# SCH_usb-hub_2024-06-10.net
KiCad netlist of a schematic drawn in EasyEDA
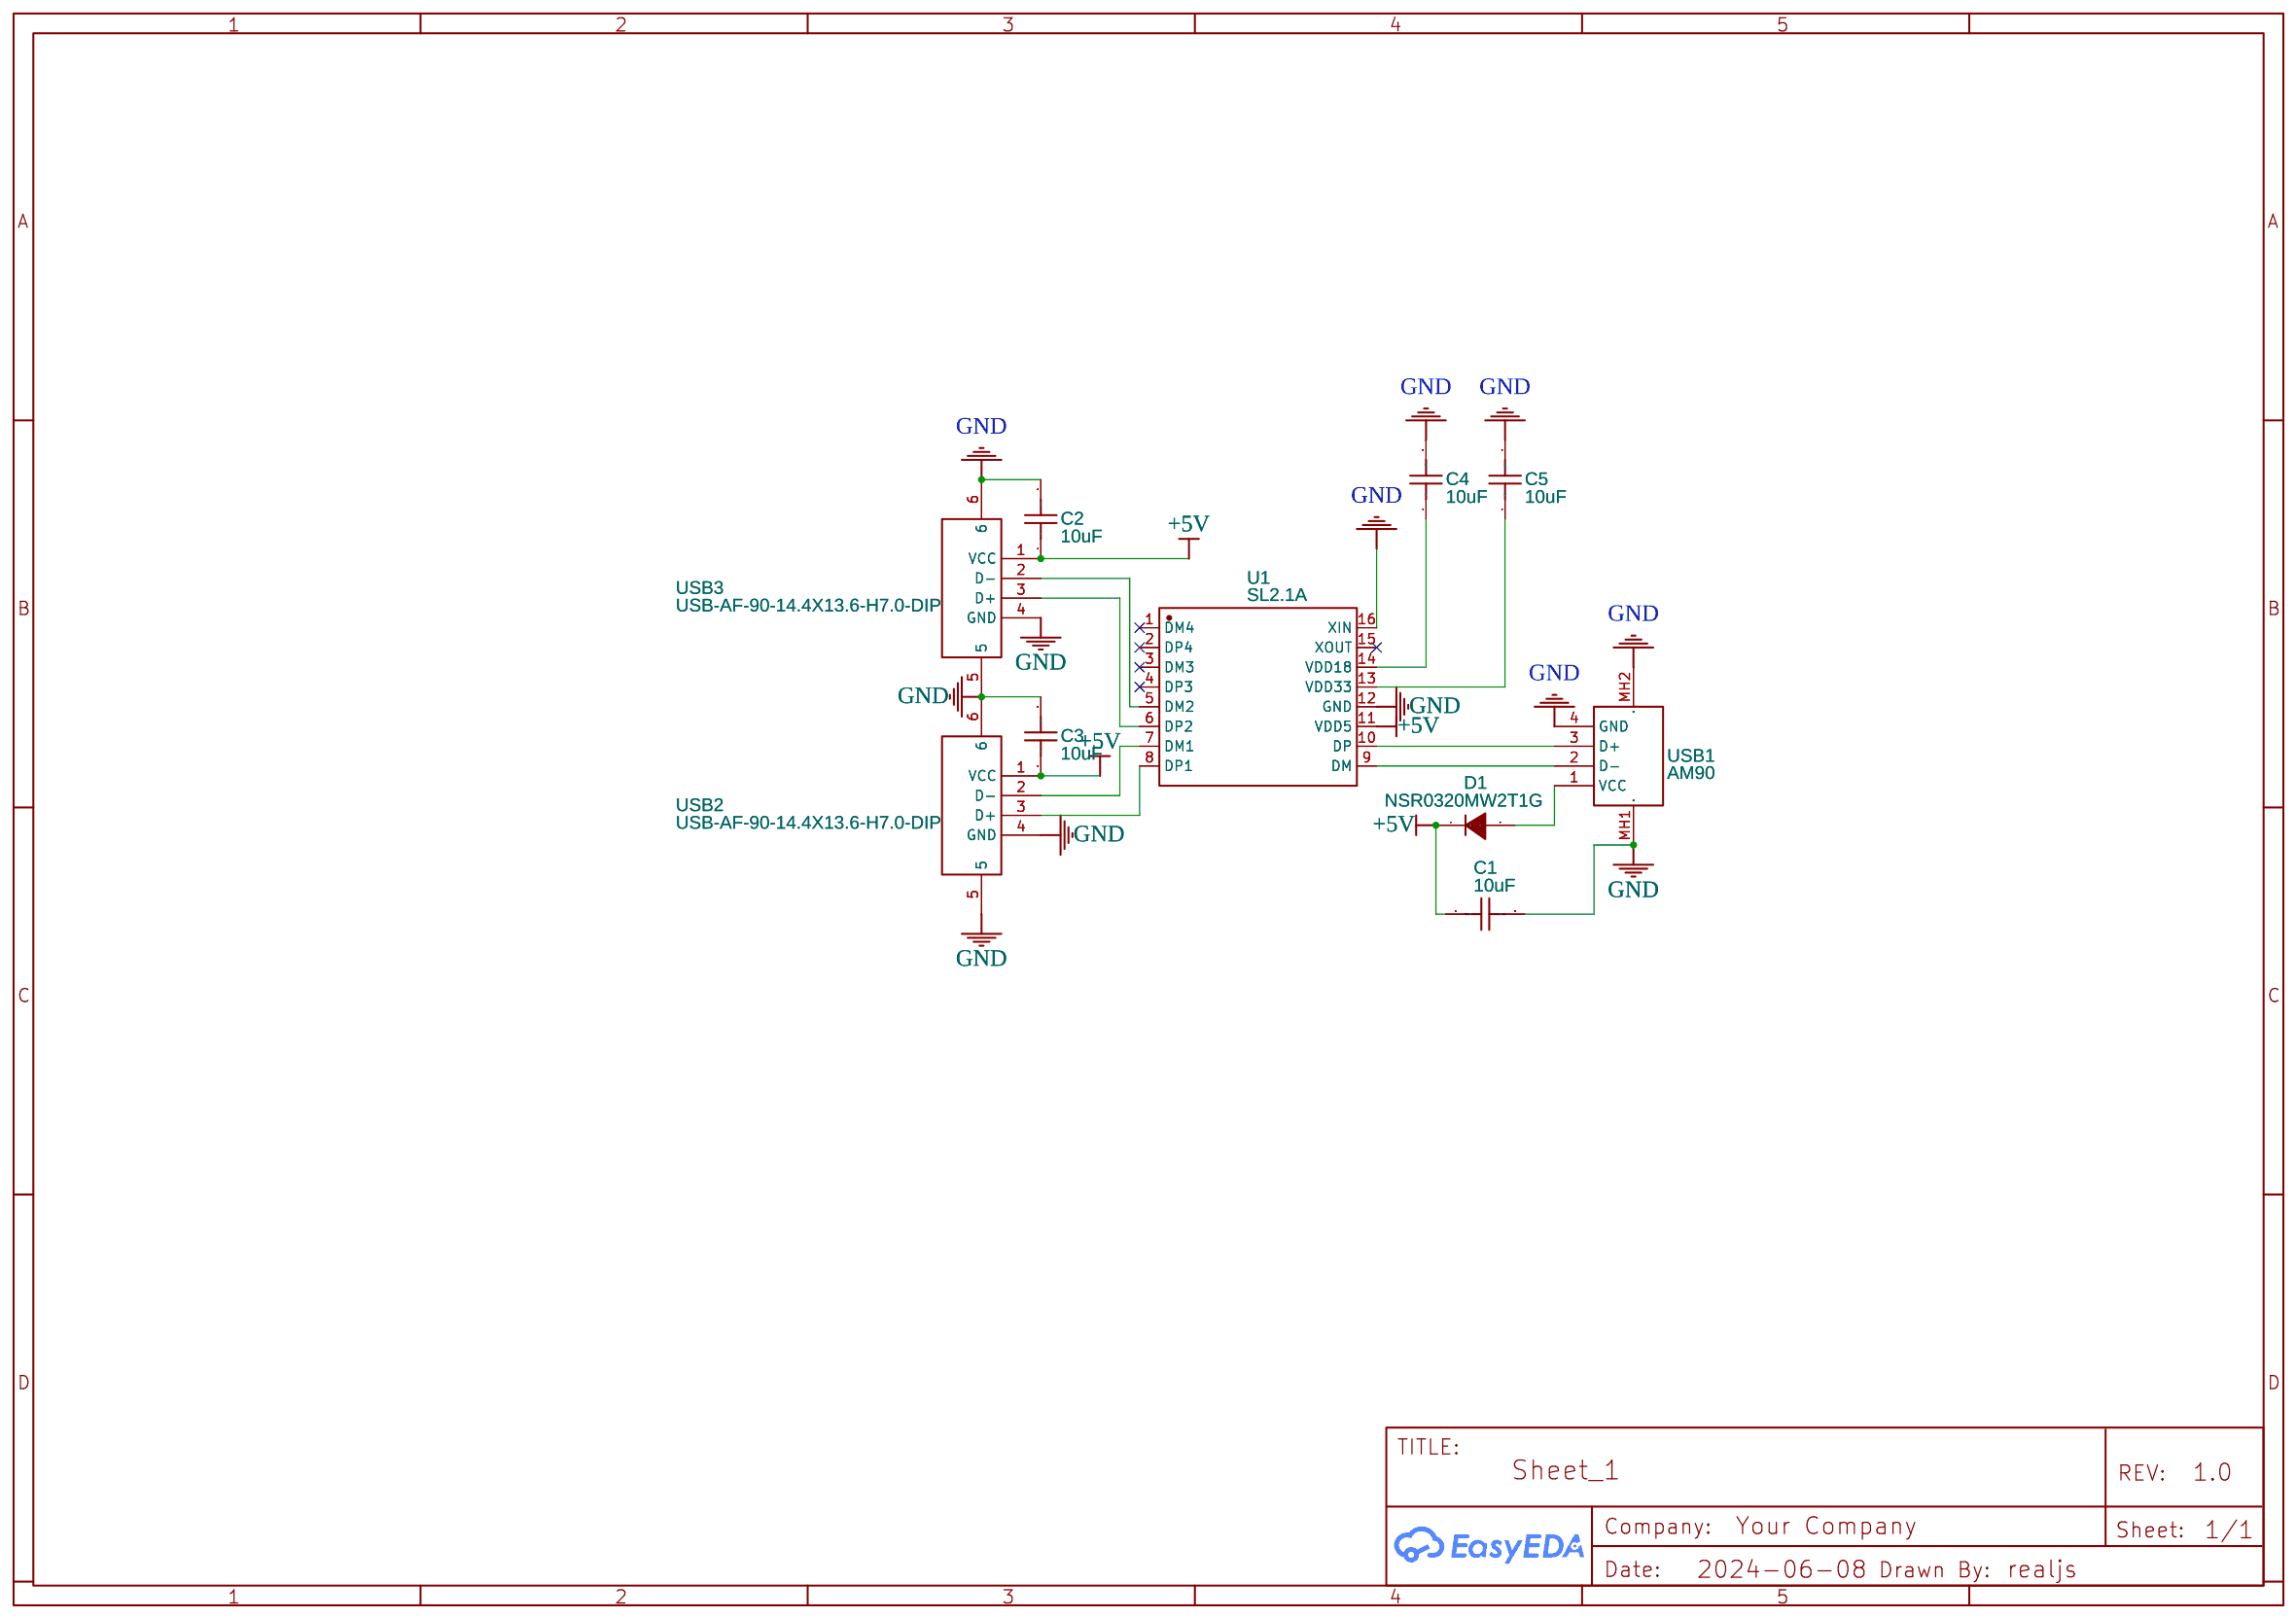
[diagram p0: schematic sheet]

(export (version "E")
  (design (tool "Eeschema 10.0.6"))
  (components
    (comp (ref "C1")
      (value "10uF")
      (fields
        (field (name "Manufacturer Part") "CL10A106KP8NNNC")
        (field (name "Manufacturer") "SAMSUNG(三星)")
      )
      (libsource (lib "") (part "CL10A106KP8NNNC_1"))
    )
    (comp (ref "C2")
      (value "10uF")
      (fields
        (field (name "Manufacturer Part") "CL10A106KP8NNNC")
        (field (name "Manufacturer") "SAMSUNG(三星)")
      )
      (libsource (lib "") (part "CL10A106KP8NNNC"))
    )
    (comp (ref "C3")
      (value "10uF")
      (fields
        (field (name "Manufacturer Part") "CL10A106KP8NNNC")
        (field (name "Manufacturer") "SAMSUNG(三星)")
      )
      (libsource (lib "") (part "CL10A106KP8NNNC"))
    )
    (comp (ref "C4")
      (value "10uF")
      (fields
        (field (name "Manufacturer Part") "CL10A106KP8NNNC")
        (field (name "Manufacturer") "SAMSUNG(三星)")
      )
      (libsource (lib "") (part "CL10A106KP8NNNC"))
    )
    (comp (ref "C5")
      (value "10uF")
      (fields
        (field (name "Manufacturer Part") "CL10A106KP8NNNC")
        (field (name "Manufacturer") "SAMSUNG(三星)")
      )
      (libsource (lib "") (part "CL10A106KP8NNNC"))
    )
    (comp (ref "D1")
      (value "NSR0320MW2T1G")
      (fields (field (name "Manufacturer") "onsemi(安森美)"))
      (libsource (lib "") (part "NSR0320MW2T1G"))
    )
    (comp (ref "U1")
      (value "SL2.1A")
      (fields (field (name "Manufacturer") "CoreChips(和芯润德)"))
      (libsource (lib "") (part "SL2.1A"))
    )
    (comp (ref "USB1")
      (value "AM90")
      (fields (field (name "Manufacturer") "SHOU HAN(首韩)"))
      (libsource (lib "") (part "AM90"))
    )
    (comp (ref "USB2")
      (value "USB-AF-90-14.4X13.6-H7.0-DIP")
      (fields (field (name "Manufacturer Part") "903-131A1011D10100") (field (name "Manufacturer") "精拓金"))
      (libsource (lib "") (part "USB-AF-90-14.4X13.6-H7.0-DIP"))
    )
    (comp (ref "USB3")
      (value "USB-AF-90-14.4X13.6-H7.0-DIP")
      (fields (field (name "Manufacturer Part") "903-131A1011D10100") (field (name "Manufacturer") "精拓金"))
      (libsource (lib "") (part "USB-AF-90-14.4X13.6-H7.0-DIP"))
    )
  )
  (nets
    (net (code "1") (name "+5V") (class "Default")
      (node (ref "C1") (pin "1") (pinfunction "1_1") (pintype "unspecified"))
      (node (ref "C2") (pin "1") (pinfunction "1_1") (pintype "unspecified"))
      (node (ref "C3") (pin "1") (pinfunction "1_1") (pintype "unspecified"))
      (node (ref "D1") (pin "1") (pinfunction "C_1") (pintype "unspecified"))
      (node (ref "U1") (pin "11") (pinfunction "VDD5_11") (pintype "unspecified"))
      (node (ref "USB2") (pin "1") (pinfunction "VCC_1") (pintype "unspecified"))
      (node (ref "USB3") (pin "1") (pinfunction "VCC_1") (pintype "unspecified"))
    )
    (net (code "2") (name "GND") (class "Default")
      (node (ref "C1") (pin "2") (pinfunction "2_2") (pintype "unspecified"))
      (node (ref "C2") (pin "2") (pinfunction "2_2") (pintype "unspecified"))
      (node (ref "C3") (pin "2") (pinfunction "2_2") (pintype "unspecified"))
      (node (ref "C4") (pin "2") (pinfunction "2_2") (pintype "unspecified"))
      (node (ref "C5") (pin "2") (pinfunction "2_2") (pintype "unspecified"))
      (node (ref "U1") (pin "12") (pinfunction "GND_12") (pintype "unspecified"))
      (node (ref "U1") (pin "16") (pinfunction "XIN_16") (pintype "unspecified"))
      (node (ref "USB1") (pin "4") (pinfunction "GND_4") (pintype "input"))
      (node (ref "USB1") (pin "MH1") (pinfunction "MH1_MH1") (pintype "unspecified"))
      (node (ref "USB1") (pin "MH2") (pinfunction "MH2_MH2") (pintype "unspecified"))
      (node (ref "USB2") (pin "4") (pinfunction "GND_4") (pintype "unspecified"))
      (node (ref "USB2") (pin "5") (pinfunction "5_5") (pintype "unspecified"))
      (node (ref "USB2") (pin "6") (pinfunction "6_6") (pintype "unspecified"))
      (node (ref "USB3") (pin "4") (pinfunction "GND_4") (pintype "unspecified"))
      (node (ref "USB3") (pin "5") (pinfunction "5_5") (pintype "unspecified"))
      (node (ref "USB3") (pin "6") (pinfunction "6_6") (pintype "unspecified"))
    )
    (net (code "3") (name "Net-(D1-A)") (class "Default")
      (node (ref "D1") (pin "2") (pinfunction "A_2") (pintype "unspecified"))
      (node (ref "USB1") (pin "1") (pinfunction "VCC_1") (pintype "input"))
    )
    (net (code "4") (name "Net-(U1-DM)") (class "Default")
      (node (ref "U1") (pin "9") (pinfunction "DM_9") (pintype "unspecified"))
      (node (ref "USB1") (pin "2") (pinfunction "D-_2") (pintype "input"))
    )
    (net (code "5") (name "Net-(U1-DM1)") (class "Default")
      (node (ref "U1") (pin "7") (pinfunction "DM1_7") (pintype "unspecified"))
      (node (ref "USB2") (pin "2") (pinfunction "D-_2") (pintype "unspecified"))
    )
    (net (code "6") (name "Net-(U1-DM2)") (class "Default")
      (node (ref "U1") (pin "5") (pinfunction "DM2_5") (pintype "unspecified"))
      (node (ref "USB3") (pin "2") (pinfunction "D-_2") (pintype "unspecified"))
    )
    (net (code "7") (name "Net-(U1-DP)") (class "Default")
      (node (ref "U1") (pin "10") (pinfunction "DP_10") (pintype "unspecified"))
      (node (ref "USB1") (pin "3") (pinfunction "D+_3") (pintype "input"))
    )
    (net (code "8") (name "Net-(U1-DP1)") (class "Default")
      (node (ref "U1") (pin "8") (pinfunction "DP1_8") (pintype "unspecified"))
      (node (ref "USB2") (pin "3") (pinfunction "D+_3") (pintype "unspecified"))
    )
    (net (code "9") (name "Net-(U1-DP2)") (class "Default")
      (node (ref "U1") (pin "6") (pinfunction "DP2_6") (pintype "unspecified"))
      (node (ref "USB3") (pin "3") (pinfunction "D+_3") (pintype "unspecified"))
    )
    (net (code "10") (name "Net-(U1-VDD18)") (class "Default")
      (node (ref "C4") (pin "1") (pinfunction "1_1") (pintype "unspecified"))
      (node (ref "U1") (pin "14") (pinfunction "VDD18_14") (pintype "unspecified"))
    )
    (net (code "11") (name "Net-(U1-VDD33)") (class "Default")
      (node (ref "C5") (pin "1") (pinfunction "1_1") (pintype "unspecified"))
      (node (ref "U1") (pin "13") (pinfunction "VDD33_13") (pintype "unspecified"))
    )
    (net (code "12") (name "unconnected-(U1-DM3-Pad3)") (class "Default")
      (node (ref "U1") (pin "3") (pinfunction "DM3_3") (pintype "unspecified+no_connect"))
    )
    (net (code "13") (name "unconnected-(U1-DM4-Pad1)") (class "Default")
      (node (ref "U1") (pin "1") (pinfunction "DM4_1") (pintype "unspecified+no_connect"))
    )
    (net (code "14") (name "unconnected-(U1-DP3-Pad4)") (class "Default")
      (node (ref "U1") (pin "4") (pinfunction "DP3_4") (pintype "unspecified+no_connect"))
    )
    (net (code "15") (name "unconnected-(U1-DP4-Pad2)") (class "Default")
      (node (ref "U1") (pin "2") (pinfunction "DP4_2") (pintype "unspecified+no_connect"))
    )
    (net (code "16") (name "unconnected-(U1-XOUT-Pad15)") (class "Default")
      (node (ref "U1") (pin "15") (pinfunction "XOUT_15") (pintype "unspecified+no_connect"))
    )
  )
)
